# DDR3_Memory_SO-DIMM.net
KiCad netlist of a schematic drawn in Altium Designer
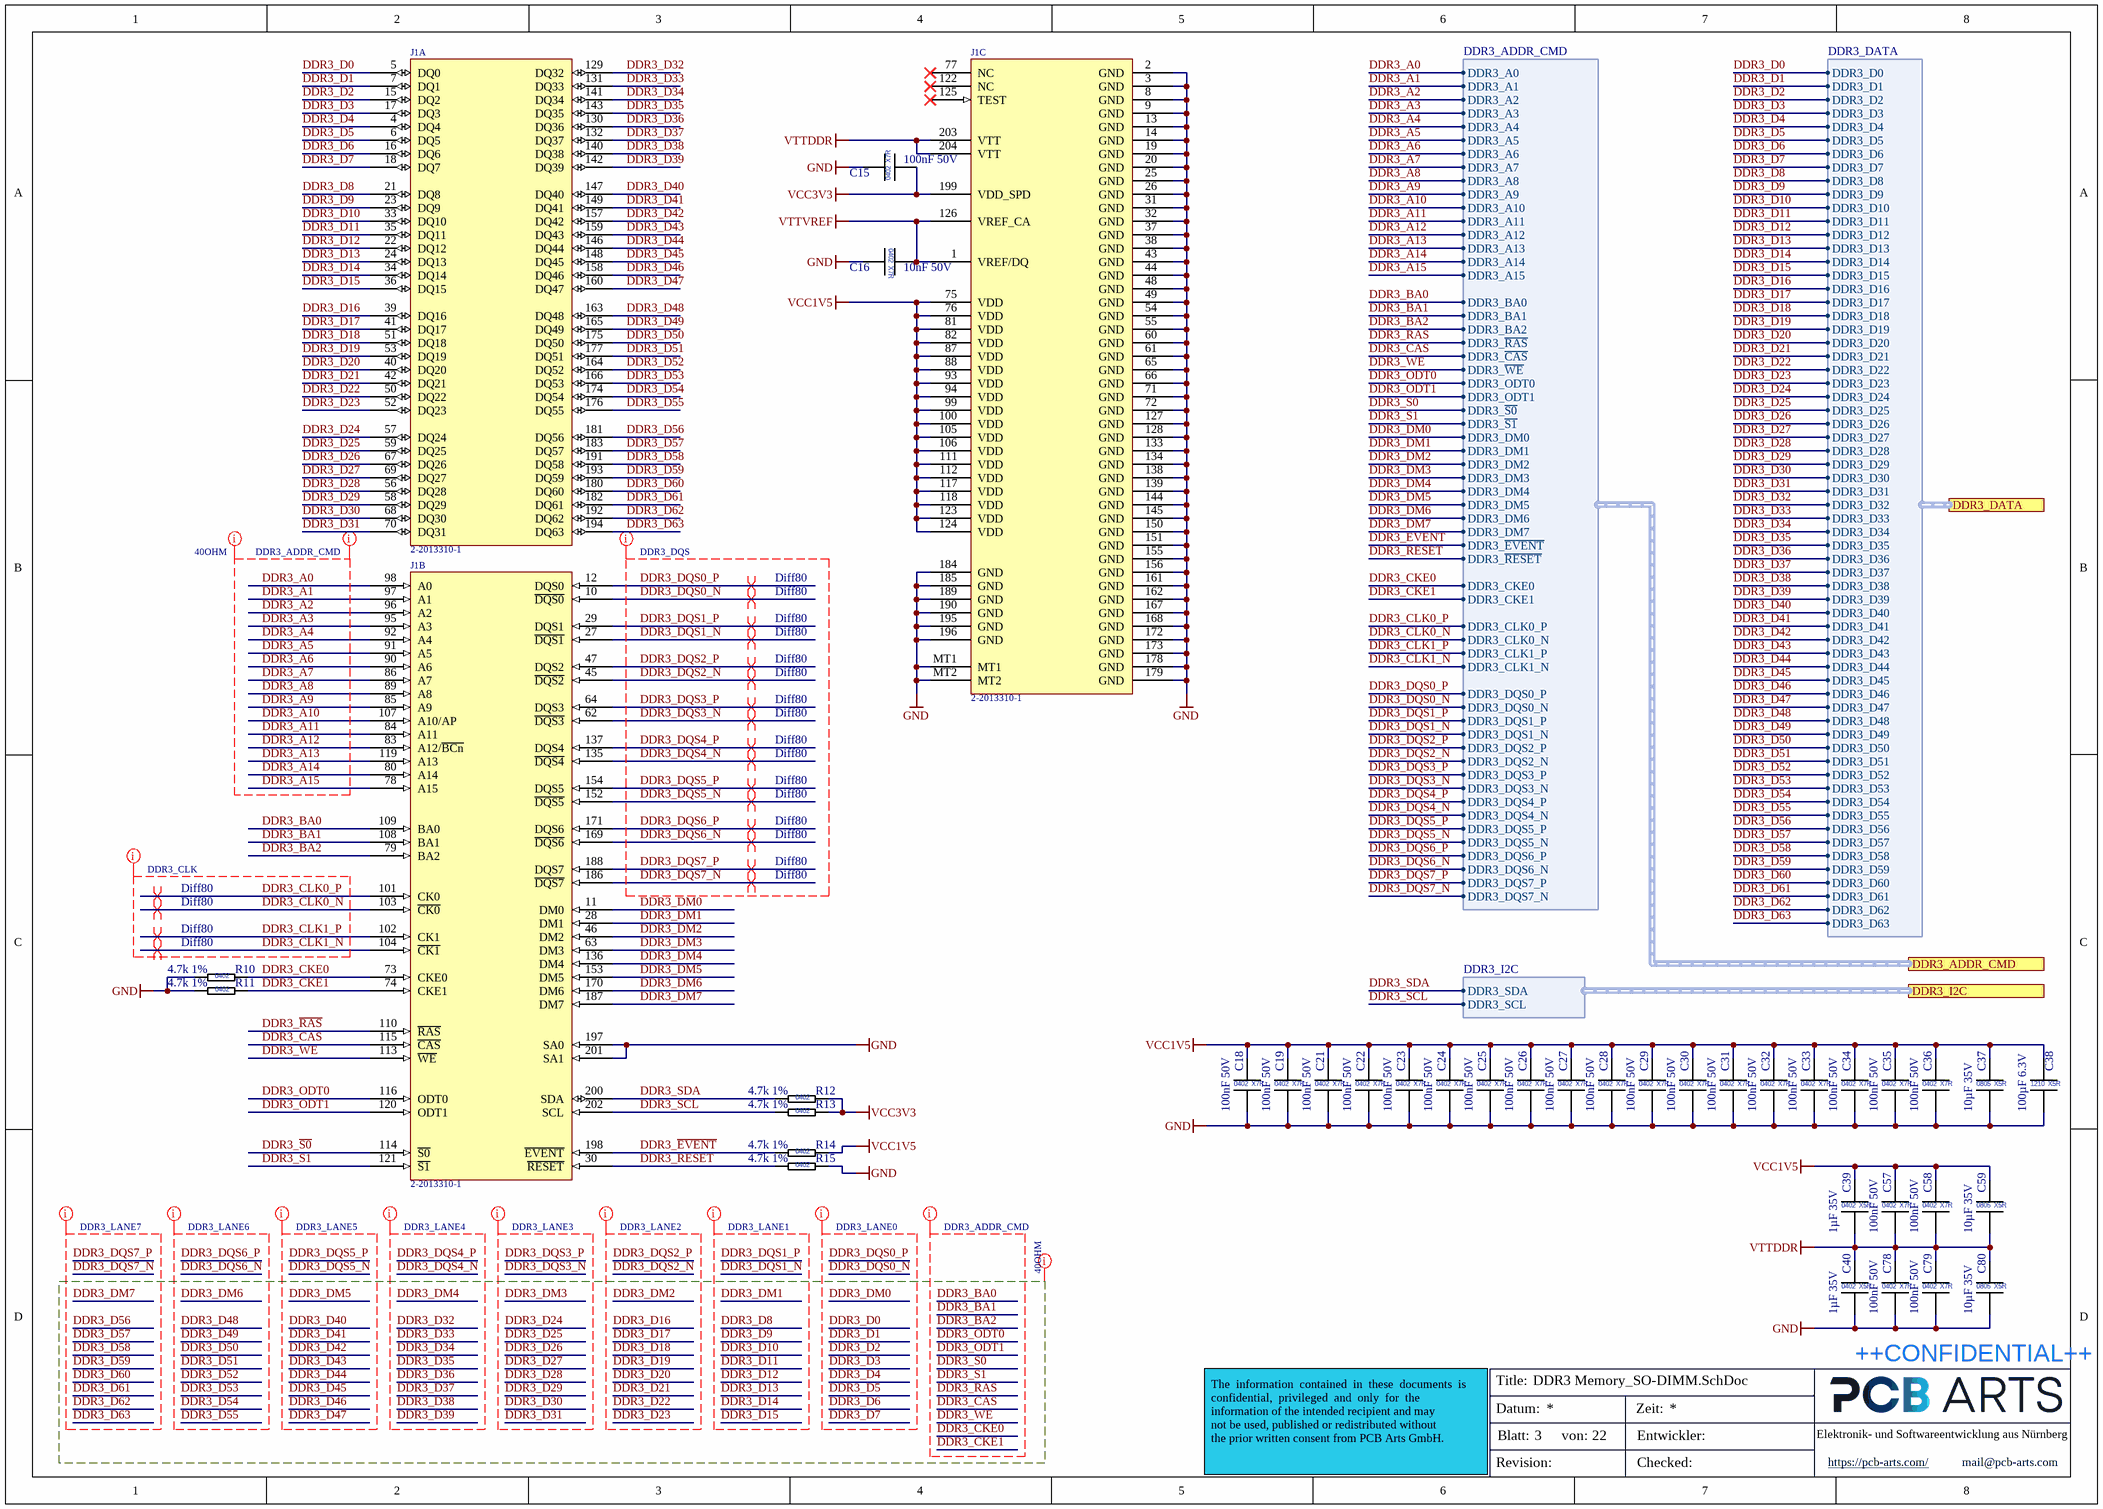
[diagram p0: DDR3 Memory_SO-DIMM.SchDoc]

(export (version "E")
  (design (tool "Eeschema 10.0.6"))
  (components
    (comp (ref "C15")
      (value "100nF 50V")
      (footprint "Cap:CAP_0402_L")
      (description "Multilayer Ceramic Capacitors MLCC - SMD/SMT 0402 50VDC")
      (libsource (lib "") (part "CAP_0402_100nF_50V_1"))
    )
    (comp (ref "C16")
      (value "10nF 50V")
      (footprint "Cap:CAP_0402_L")
      (description "Multilayer Ceramic Capacitors MLCC - SMD/SMT 0402 50VDC")
      (libsource (lib "Cap") (part "CAP_0402_10nF_50V"))
    )
    (comp (ref "C18")
      (value "100nF 50V")
      (footprint "Cap:CAP_0402_L")
      (description "Multilayer Ceramic Capacitors MLCC - SMD/SMT 0402 50VDC")
      (libsource (lib "Cap") (part "CAP_0402_100nF_50V"))
    )
    (comp (ref "C19")
      (value "100nF 50V")
      (footprint "Cap:CAP_0402_L")
      (description "Multilayer Ceramic Capacitors MLCC - SMD/SMT 0402 50VDC")
      (libsource (lib "Cap") (part "CAP_0402_100nF_50V"))
    )
    (comp (ref "C21")
      (value "100nF 50V")
      (footprint "Cap:CAP_0402_L")
      (description "Multilayer Ceramic Capacitors MLCC - SMD/SMT 0402 50VDC")
      (libsource (lib "Cap") (part "CAP_0402_100nF_50V"))
    )
    (comp (ref "C22")
      (value "100nF 50V")
      (footprint "Cap:CAP_0402_L")
      (description "Multilayer Ceramic Capacitors MLCC - SMD/SMT 0402 50VDC")
      (libsource (lib "Cap") (part "CAP_0402_100nF_50V"))
    )
    (comp (ref "C23")
      (value "100nF 50V")
      (footprint "Cap:CAP_0402_L")
      (description "Multilayer Ceramic Capacitors MLCC - SMD/SMT 0402 50VDC")
      (libsource (lib "Cap") (part "CAP_0402_100nF_50V"))
    )
    (comp (ref "C24")
      (value "100nF 50V")
      (footprint "Cap:CAP_0402_L")
      (description "Multilayer Ceramic Capacitors MLCC - SMD/SMT 0402 50VDC")
      (libsource (lib "Cap") (part "CAP_0402_100nF_50V"))
    )
    (comp (ref "C25")
      (value "100nF 50V")
      (footprint "Cap:CAP_0402_L")
      (description "Multilayer Ceramic Capacitors MLCC - SMD/SMT 0402 50VDC")
      (libsource (lib "Cap") (part "CAP_0402_100nF_50V"))
    )
    (comp (ref "C26")
      (value "100nF 50V")
      (footprint "Cap:CAP_0402_L")
      (description "Multilayer Ceramic Capacitors MLCC - SMD/SMT 0402 50VDC")
      (libsource (lib "Cap") (part "CAP_0402_100nF_50V"))
    )
    (comp (ref "C27")
      (value "100nF 50V")
      (footprint "Cap:CAP_0402_L")
      (description "Multilayer Ceramic Capacitors MLCC - SMD/SMT 0402 50VDC")
      (libsource (lib "Cap") (part "CAP_0402_100nF_50V"))
    )
    (comp (ref "C28")
      (value "100nF 50V")
      (footprint "Cap:CAP_0402_L")
      (description "Multilayer Ceramic Capacitors MLCC - SMD/SMT 0402 50VDC")
      (libsource (lib "Cap") (part "CAP_0402_100nF_50V"))
    )
    (comp (ref "C29")
      (value "100nF 50V")
      (footprint "Cap:CAP_0402_L")
      (description "Multilayer Ceramic Capacitors MLCC - SMD/SMT 0402 50VDC")
      (libsource (lib "Cap") (part "CAP_0402_100nF_50V"))
    )
    (comp (ref "C30")
      (value "100nF 50V")
      (footprint "Cap:CAP_0402_L")
      (description "Multilayer Ceramic Capacitors MLCC - SMD/SMT 0402 50VDC")
      (libsource (lib "Cap") (part "CAP_0402_100nF_50V"))
    )
    (comp (ref "C31")
      (value "100nF 50V")
      (footprint "Cap:CAP_0402_L")
      (description "Multilayer Ceramic Capacitors MLCC - SMD/SMT 0402 50VDC")
      (libsource (lib "Cap") (part "CAP_0402_100nF_50V"))
    )
    (comp (ref "C32")
      (value "100nF 50V")
      (footprint "Cap:CAP_0402_L")
      (description "Multilayer Ceramic Capacitors MLCC - SMD/SMT 0402 50VDC")
      (libsource (lib "Cap") (part "CAP_0402_100nF_50V"))
    )
    (comp (ref "C33")
      (value "100nF 50V")
      (footprint "Cap:CAP_0402_L")
      (description "Multilayer Ceramic Capacitors MLCC - SMD/SMT 0402 50VDC")
      (libsource (lib "Cap") (part "CAP_0402_100nF_50V"))
    )
    (comp (ref "C34")
      (value "100nF 50V")
      (footprint "Cap:CAP_0402_L")
      (description "Multilayer Ceramic Capacitors MLCC - SMD/SMT 0402 50VDC")
      (libsource (lib "Cap") (part "CAP_0402_100nF_50V"))
    )
    (comp (ref "C35")
      (value "100nF 50V")
      (footprint "Cap:CAP_0402_L")
      (description "Multilayer Ceramic Capacitors MLCC - SMD/SMT 0402 50VDC")
      (libsource (lib "Cap") (part "CAP_0402_100nF_50V"))
    )
    (comp (ref "C36")
      (value "100nF 50V")
      (footprint "Cap:CAP_0402_L")
      (description "Multilayer Ceramic Capacitors MLCC - SMD/SMT 0402 50VDC")
      (libsource (lib "Cap") (part "CAP_0402_100nF_50V"))
    )
    (comp (ref "C37")
      (value "10µF 35V")
      (footprint "Cap:CAP_0805")
      (description "Multilayer Ceramic Capacitors MLCC - SMD/SMT 0805 35VDC")
      (libsource (lib "Cap") (part "CAP_0805_10µF_35V"))
    )
    (comp (ref "C38")
      (value "100µF 6.3V")
      (footprint "Cap:CAP_1210")
      (description "Multilayer Ceramic Capacitors MLCC - SMD/SMT 1210 6.3VDC")
      (libsource (lib "Cap") (part "CAP_1210_100µF_6.3V"))
    )
    (comp (ref "C39")
      (value "1µF 35V")
      (footprint "Cap:CAP_0402_L")
      (description "Multilayer Ceramic Capacitors MLCC - SMD/SMT 0402 35VDC")
      (libsource (lib "Cap") (part "CAP_0402_1µF_35V"))
    )
    (comp (ref "C40")
      (value "1µF 35V")
      (footprint "Cap:CAP_0402_L")
      (description "Multilayer Ceramic Capacitors MLCC - SMD/SMT 0402 35VDC")
      (libsource (lib "Cap") (part "CAP_0402_1µF_35V"))
    )
    (comp (ref "C57")
      (value "100nF 50V")
      (footprint "Cap:CAP_0402_L")
      (description "Multilayer Ceramic Capacitors MLCC - SMD/SMT 0402 50VDC")
      (libsource (lib "Cap") (part "CAP_0402_100nF_50V"))
    )
    (comp (ref "C58")
      (value "100nF 50V")
      (footprint "Cap:CAP_0402_L")
      (description "Multilayer Ceramic Capacitors MLCC - SMD/SMT 0402 50VDC")
      (libsource (lib "Cap") (part "CAP_0402_100nF_50V"))
    )
    (comp (ref "C59")
      (value "10µF 35V")
      (footprint "Cap:CAP_0805")
      (description "Multilayer Ceramic Capacitors MLCC - SMD/SMT 0805 35VDC")
      (libsource (lib "Cap") (part "CAP_0805_10µF_35V"))
    )
    (comp (ref "C78")
      (value "100nF 50V")
      (footprint "Cap:CAP_0402_L")
      (description "Multilayer Ceramic Capacitors MLCC - SMD/SMT 0402 50VDC")
      (libsource (lib "Cap") (part "CAP_0402_100nF_50V"))
    )
    (comp (ref "C79")
      (value "100nF 50V")
      (footprint "Cap:CAP_0402_L")
      (description "Multilayer Ceramic Capacitors MLCC - SMD/SMT 0402 50VDC")
      (libsource (lib "Cap") (part "CAP_0402_100nF_50V"))
    )
    (comp (ref "C80")
      (value "10µF 35V")
      (footprint "Cap:CAP_0805")
      (description "Multilayer Ceramic Capacitors MLCC - SMD/SMT 0805 35VDC")
      (libsource (lib "Cap") (part "CAP_0805_10µF_35V"))
    )
    (comp (ref "J1")
      (value "2-2013310-1")
      (footprint "Conn:2-2013310-1")
      (description "SO-DIMM DDR3 204P 9.2H STD Connector")
      (libsource (lib "Conn") (part "2-2013310-1_SO-DIMM DDR3 204P 9.2H STD Connector"))
    )
    (comp (ref "R10")
      (value "4.7k 1%")
      (footprint "Res:RES_0402_L")
      (description "Thick Film Resistors - SMD 4.7kOhm 1%")
      (libsource (lib "Res") (part "RES_0402_4.7k_1%"))
    )
    (comp (ref "R11")
      (value "4.7k 1%")
      (footprint "Res:RES_0402_L")
      (description "Thick Film Resistors - SMD 4.7kOhm 1%")
      (libsource (lib "Res") (part "RES_0402_4.7k_1%"))
    )
    (comp (ref "R12")
      (value "4.7k 1%")
      (footprint "Res:RES_0402_L")
      (description "Thick Film Resistors - SMD 4.7kOhm 1%")
      (libsource (lib "Res") (part "RES_0402_4.7k_1%"))
    )
    (comp (ref "R13")
      (value "4.7k 1%")
      (footprint "Res:RES_0402_L")
      (description "Thick Film Resistors - SMD 4.7kOhm 1%")
      (libsource (lib "Res") (part "RES_0402_4.7k_1%"))
    )
    (comp (ref "R14")
      (value "4.7k 1%")
      (footprint "Res:RES_0402_L")
      (description "Thick Film Resistors - SMD 4.7kOhm 1%")
      (libsource (lib "Res") (part "RES_0402_4.7k_1%"))
    )
    (comp (ref "R15")
      (value "4.7k 1%")
      (footprint "Res:RES_0402_L")
      (description "Thick Film Resistors - SMD 4.7kOhm 1%")
      (libsource (lib "Res") (part "RES_0402_4.7k_1%"))
    )
  )
  (nets
    (net (code "4") (name "/DDR3_A0") (class "Default")
      (node (ref "J1") (pin "98") (pinfunction "A0_98") (pintype "input"))
    )
    (net (code "5") (name "/DDR3_A1") (class "Default")
      (node (ref "J1") (pin "97") (pinfunction "A1_97") (pintype "input"))
    )
    (net (code "6") (name "/DDR3_A2") (class "Default")
      (node (ref "J1") (pin "96") (pinfunction "A2_96") (pintype "input"))
    )
    (net (code "7") (name "/DDR3_A3") (class "Default")
      (node (ref "J1") (pin "95") (pinfunction "A3_95") (pintype "input"))
    )
    (net (code "8") (name "/DDR3_A4") (class "Default")
      (node (ref "J1") (pin "92") (pinfunction "A4_92") (pintype "input"))
    )
    (net (code "9") (name "/DDR3_A5") (class "Default")
      (node (ref "J1") (pin "91") (pinfunction "A5_91") (pintype "input"))
    )
    (net (code "10") (name "/DDR3_A6") (class "Default")
      (node (ref "J1") (pin "90") (pinfunction "A6_90") (pintype "input"))
    )
    (net (code "11") (name "/DDR3_A7") (class "Default")
      (node (ref "J1") (pin "86") (pinfunction "A7_86") (pintype "input"))
    )
    (net (code "12") (name "/DDR3_A8") (class "Default")
      (node (ref "J1") (pin "89") (pinfunction "A8_89") (pintype "input"))
    )
    (net (code "13") (name "/DDR3_A9") (class "Default")
      (node (ref "J1") (pin "85") (pinfunction "A9_85") (pintype "input"))
    )
    (net (code "14") (name "/DDR3_A10") (class "Default")
      (node (ref "J1") (pin "107") (pinfunction "A10/AP_107") (pintype "input"))
    )
    (net (code "15") (name "/DDR3_A11") (class "Default")
      (node (ref "J1") (pin "84") (pinfunction "A11_84") (pintype "input"))
    )
    (net (code "16") (name "/DDR3_A12") (class "Default")
      (node (ref "J1") (pin "83") (pinfunction "A12/~{BCn}_83") (pintype "input"))
    )
    (net (code "17") (name "/DDR3_A13") (class "Default")
      (node (ref "J1") (pin "119") (pinfunction "A13_119") (pintype "input"))
    )
    (net (code "18") (name "/DDR3_A14") (class "Default")
      (node (ref "J1") (pin "80") (pinfunction "A14_80") (pintype "input"))
    )
    (net (code "19") (name "/DDR3_A15") (class "Default")
      (node (ref "J1") (pin "78") (pinfunction "A15_78") (pintype "input"))
    )
    (net (code "20") (name "/DDR3_BA0") (class "Default")
      (node (ref "J1") (pin "109") (pinfunction "BA0_109") (pintype "input"))
    )
    (net (code "21") (name "/DDR3_BA1") (class "Default")
      (node (ref "J1") (pin "108") (pinfunction "BA1_108") (pintype "input"))
    )
    (net (code "22") (name "/DDR3_BA2") (class "Default")
      (node (ref "J1") (pin "79") (pinfunction "BA2_79") (pintype "input"))
    )
    (net (code "23") (name "/DDR3_CKE0") (class "Default")
      (node (ref "J1") (pin "73") (pinfunction "CKE0_73") (pintype "input"))
      (node (ref "R10") (pin "2") (pinfunction "2_2") (pintype "passive"))
    )
    (net (code "24") (name "/DDR3_CKE1") (class "Default")
      (node (ref "J1") (pin "74") (pinfunction "CKE1_74") (pintype "input"))
      (node (ref "R11") (pin "2") (pinfunction "2_2") (pintype "passive"))
    )
    (net (code "25") (name "/DDR3_CLK0_N") (class "Default")
      (node (ref "J1") (pin "103") (pinfunction "~{CK0}_103") (pintype "input"))
    )
    (net (code "26") (name "/DDR3_CLK0_P") (class "Default")
      (node (ref "J1") (pin "101") (pinfunction "CK0_101") (pintype "input"))
    )
    (net (code "27") (name "/DDR3_CLK1_N") (class "Default")
      (node (ref "J1") (pin "104") (pinfunction "~{CK1}_104") (pintype "input"))
    )
    (net (code "28") (name "/DDR3_CLK1_P") (class "Default")
      (node (ref "J1") (pin "102") (pinfunction "CK1_102") (pintype "input"))
    )
    (net (code "29") (name "/DDR3_D0") (class "Default")
      (node (ref "J1") (pin "5") (pinfunction "DQ0_5") (pintype "bidirectional"))
    )
    (net (code "30") (name "/DDR3_D1") (class "Default")
      (node (ref "J1") (pin "7") (pinfunction "DQ1_7") (pintype "bidirectional"))
    )
    (net (code "31") (name "/DDR3_D2") (class "Default")
      (node (ref "J1") (pin "15") (pinfunction "DQ2_15") (pintype "bidirectional"))
    )
    (net (code "32") (name "/DDR3_D3") (class "Default")
      (node (ref "J1") (pin "17") (pinfunction "DQ3_17") (pintype "bidirectional"))
    )
    (net (code "33") (name "/DDR3_D4") (class "Default")
      (node (ref "J1") (pin "4") (pinfunction "DQ4_4") (pintype "bidirectional"))
    )
    (net (code "34") (name "/DDR3_D5") (class "Default")
      (node (ref "J1") (pin "6") (pinfunction "DQ5_6") (pintype "bidirectional"))
    )
    (net (code "35") (name "/DDR3_D6") (class "Default")
      (node (ref "J1") (pin "16") (pinfunction "DQ6_16") (pintype "bidirectional"))
    )
    (net (code "36") (name "/DDR3_D7") (class "Default")
      (node (ref "J1") (pin "18") (pinfunction "DQ7_18") (pintype "bidirectional"))
    )
    (net (code "37") (name "/DDR3_D8") (class "Default")
      (node (ref "J1") (pin "21") (pinfunction "DQ8_21") (pintype "bidirectional"))
    )
    (net (code "38") (name "/DDR3_D9") (class "Default")
      (node (ref "J1") (pin "23") (pinfunction "DQ9_23") (pintype "bidirectional"))
    )
    (net (code "39") (name "/DDR3_D10") (class "Default")
      (node (ref "J1") (pin "33") (pinfunction "DQ10_33") (pintype "bidirectional"))
    )
    (net (code "40") (name "/DDR3_D11") (class "Default")
      (node (ref "J1") (pin "35") (pinfunction "DQ11_35") (pintype "bidirectional"))
    )
    (net (code "41") (name "/DDR3_D12") (class "Default")
      (node (ref "J1") (pin "22") (pinfunction "DQ12_22") (pintype "bidirectional"))
    )
    (net (code "42") (name "/DDR3_D13") (class "Default")
      (node (ref "J1") (pin "24") (pinfunction "DQ13_24") (pintype "bidirectional"))
    )
    (net (code "43") (name "/DDR3_D14") (class "Default")
      (node (ref "J1") (pin "34") (pinfunction "DQ14_34") (pintype "bidirectional"))
    )
    (net (code "44") (name "/DDR3_D15") (class "Default")
      (node (ref "J1") (pin "36") (pinfunction "DQ15_36") (pintype "bidirectional"))
    )
    (net (code "45") (name "/DDR3_D16") (class "Default")
      (node (ref "J1") (pin "39") (pinfunction "DQ16_39") (pintype "bidirectional"))
    )
    (net (code "46") (name "/DDR3_D17") (class "Default")
      (node (ref "J1") (pin "41") (pinfunction "DQ17_41") (pintype "bidirectional"))
    )
    (net (code "47") (name "/DDR3_D18") (class "Default")
      (node (ref "J1") (pin "51") (pinfunction "DQ18_51") (pintype "bidirectional"))
    )
    (net (code "48") (name "/DDR3_D19") (class "Default")
      (node (ref "J1") (pin "53") (pinfunction "DQ19_53") (pintype "bidirectional"))
    )
    (net (code "49") (name "/DDR3_D20") (class "Default")
      (node (ref "J1") (pin "40") (pinfunction "DQ20_40") (pintype "bidirectional"))
    )
    (net (code "50") (name "/DDR3_D21") (class "Default")
      (node (ref "J1") (pin "42") (pinfunction "DQ21_42") (pintype "bidirectional"))
    )
    (net (code "51") (name "/DDR3_D22") (class "Default")
      (node (ref "J1") (pin "50") (pinfunction "DQ22_50") (pintype "bidirectional"))
    )
    (net (code "52") (name "/DDR3_D23") (class "Default")
      (node (ref "J1") (pin "52") (pinfunction "DQ23_52") (pintype "bidirectional"))
    )
    (net (code "53") (name "/DDR3_D24") (class "Default")
      (node (ref "J1") (pin "57") (pinfunction "DQ24_57") (pintype "bidirectional"))
    )
    (net (code "54") (name "/DDR3_D25") (class "Default")
      (node (ref "J1") (pin "59") (pinfunction "DQ25_59") (pintype "bidirectional"))
    )
    (net (code "55") (name "/DDR3_D26") (class "Default")
      (node (ref "J1") (pin "67") (pinfunction "DQ26_67") (pintype "bidirectional"))
    )
    (net (code "56") (name "/DDR3_D27") (class "Default")
      (node (ref "J1") (pin "69") (pinfunction "DQ27_69") (pintype "bidirectional"))
    )
    (net (code "57") (name "/DDR3_D28") (class "Default")
      (node (ref "J1") (pin "56") (pinfunction "DQ28_56") (pintype "bidirectional"))
    )
    (net (code "58") (name "/DDR3_D29") (class "Default")
      (node (ref "J1") (pin "58") (pinfunction "DQ29_58") (pintype "bidirectional"))
    )
    (net (code "59") (name "/DDR3_D30") (class "Default")
      (node (ref "J1") (pin "68") (pinfunction "DQ30_68") (pintype "bidirectional"))
    )
    (net (code "60") (name "/DDR3_D31") (class "Default")
      (node (ref "J1") (pin "70") (pinfunction "DQ31_70") (pintype "bidirectional"))
    )
    (net (code "61") (name "/DDR3_D32") (class "Default")
      (node (ref "J1") (pin "129") (pinfunction "DQ32_129") (pintype "bidirectional"))
    )
    (net (code "62") (name "/DDR3_D33") (class "Default")
      (node (ref "J1") (pin "131") (pinfunction "DQ33_131") (pintype "bidirectional"))
    )
    (net (code "63") (name "/DDR3_D34") (class "Default")
      (node (ref "J1") (pin "141") (pinfunction "DQ34_141") (pintype "bidirectional"))
    )
    (net (code "64") (name "/DDR3_D35") (class "Default")
      (node (ref "J1") (pin "143") (pinfunction "DQ35_143") (pintype "bidirectional"))
    )
    (net (code "65") (name "/DDR3_D36") (class "Default")
      (node (ref "J1") (pin "130") (pinfunction "DQ36_130") (pintype "bidirectional"))
    )
    (net (code "66") (name "/DDR3_D37") (class "Default")
      (node (ref "J1") (pin "132") (pinfunction "DQ37_132") (pintype "bidirectional"))
    )
    (net (code "67") (name "/DDR3_D38") (class "Default")
      (node (ref "J1") (pin "140") (pinfunction "DQ38_140") (pintype "bidirectional"))
    )
    (net (code "68") (name "/DDR3_D39") (class "Default")
      (node (ref "J1") (pin "142") (pinfunction "DQ39_142") (pintype "bidirectional"))
    )
    (net (code "69") (name "/DDR3_D40") (class "Default")
      (node (ref "J1") (pin "147") (pinfunction "DQ40_147") (pintype "bidirectional"))
    )
    (net (code "70") (name "/DDR3_D41") (class "Default")
      (node (ref "J1") (pin "149") (pinfunction "DQ41_149") (pintype "bidirectional"))
    )
    (net (code "71") (name "/DDR3_D42") (class "Default")
      (node (ref "J1") (pin "157") (pinfunction "DQ42_157") (pintype "bidirectional"))
    )
    (net (code "72") (name "/DDR3_D43") (class "Default")
      (node (ref "J1") (pin "159") (pinfunction "DQ43_159") (pintype "bidirectional"))
    )
    (net (code "73") (name "/DDR3_D44") (class "Default")
      (node (ref "J1") (pin "146") (pinfunction "DQ44_146") (pintype "bidirectional"))
    )
    (net (code "74") (name "/DDR3_D45") (class "Default")
      (node (ref "J1") (pin "148") (pinfunction "DQ45_148") (pintype "bidirectional"))
    )
    (net (code "75") (name "/DDR3_D46") (class "Default")
      (node (ref "J1") (pin "158") (pinfunction "DQ46_158") (pintype "bidirectional"))
    )
    (net (code "76") (name "/DDR3_D47") (class "Default")
      (node (ref "J1") (pin "160") (pinfunction "DQ47_160") (pintype "bidirectional"))
    )
    (net (code "77") (name "/DDR3_D48") (class "Default")
      (node (ref "J1") (pin "163") (pinfunction "DQ48_163") (pintype "bidirectional"))
    )
    (net (code "78") (name "/DDR3_D49") (class "Default")
      (node (ref "J1") (pin "165") (pinfunction "DQ49_165") (pintype "bidirectional"))
    )
    (net (code "79") (name "/DDR3_D50") (class "Default")
      (node (ref "J1") (pin "175") (pinfunction "DQ50_175") (pintype "bidirectional"))
    )
    (net (code "80") (name "/DDR3_D51") (class "Default")
      (node (ref "J1") (pin "177") (pinfunction "DQ51_177") (pintype "bidirectional"))
    )
    (net (code "81") (name "/DDR3_D52") (class "Default")
      (node (ref "J1") (pin "164") (pinfunction "DQ52_164") (pintype "bidirectional"))
    )
    (net (code "82") (name "/DDR3_D53") (class "Default")
      (node (ref "J1") (pin "166") (pinfunction "DQ53_166") (pintype "bidirectional"))
    )
    (net (code "83") (name "/DDR3_D54") (class "Default")
      (node (ref "J1") (pin "174") (pinfunction "DQ54_174") (pintype "bidirectional"))
    )
    (net (code "84") (name "/DDR3_D55") (class "Default")
      (node (ref "J1") (pin "176") (pinfunction "DQ55_176") (pintype "bidirectional"))
    )
    (net (code "85") (name "/DDR3_D56") (class "Default")
      (node (ref "J1") (pin "181") (pinfunction "DQ56_181") (pintype "bidirectional"))
    )
    (net (code "86") (name "/DDR3_D57") (class "Default")
      (node (ref "J1") (pin "183") (pinfunction "DQ57_183") (pintype "bidirectional"))
    )
    (net (code "87") (name "/DDR3_D58") (class "Default")
      (node (ref "J1") (pin "191") (pinfunction "DQ58_191") (pintype "bidirectional"))
    )
    (net (code "88") (name "/DDR3_D59") (class "Default")
      (node (ref "J1") (pin "193") (pinfunction "DQ59_193") (pintype "bidirectional"))
    )
    (net (code "89") (name "/DDR3_D60") (class "Default")
      (node (ref "J1") (pin "180") (pinfunction "DQ60_180") (pintype "bidirectional"))
    )
    (net (code "90") (name "/DDR3_D61") (class "Default")
      (node (ref "J1") (pin "182") (pinfunction "DQ61_182") (pintype "bidirectional"))
    )
    (net (code "91") (name "/DDR3_D62") (class "Default")
      (node (ref "J1") (pin "192") (pinfunction "DQ62_192") (pintype "bidirectional"))
    )
    (net (code "92") (name "/DDR3_D63") (class "Default")
      (node (ref "J1") (pin "194") (pinfunction "DQ63_194") (pintype "bidirectional"))
    )
    (net (code "93") (name "/DDR3_DM0") (class "Default")
      (node (ref "J1") (pin "11") (pinfunction "DM0_11") (pintype "input"))
    )
    (net (code "94") (name "/DDR3_DM1") (class "Default")
      (node (ref "J1") (pin "28") (pinfunction "DM1_28") (pintype "input"))
    )
    (net (code "95") (name "/DDR3_DM2") (class "Default")
      (node (ref "J1") (pin "46") (pinfunction "DM2_46") (pintype "input"))
    )
    (net (code "96") (name "/DDR3_DM3") (class "Default")
      (node (ref "J1") (pin "63") (pinfunction "DM3_63") (pintype "input"))
    )
    (net (code "97") (name "/DDR3_DM4") (class "Default")
      (node (ref "J1") (pin "136") (pinfunction "DM4_136") (pintype "input"))
    )
    (net (code "98") (name "/DDR3_DM5") (class "Default")
      (node (ref "J1") (pin "153") (pinfunction "DM5_153") (pintype "input"))
    )
    (net (code "99") (name "/DDR3_DM6") (class "Default")
      (node (ref "J1") (pin "170") (pinfunction "DM6_170") (pintype "input"))
    )
    (net (code "100") (name "/DDR3_DM7") (class "Default")
      (node (ref "J1") (pin "187") (pinfunction "DM7_187") (pintype "input"))
    )
    (net (code "101") (name "/DDR3_DQS0_N") (class "Default")
      (node (ref "J1") (pin "10") (pinfunction "~{DQS0}_10") (pintype "input"))
    )
    (net (code "102") (name "/DDR3_DQS0_P") (class "Default")
      (node (ref "J1") (pin "12") (pinfunction "DQS0_12") (pintype "input"))
    )
    (net (code "103") (name "/DDR3_DQS1_N") (class "Default")
      (node (ref "J1") (pin "27") (pinfunction "~{DQS1}_27") (pintype "input"))
    )
    (net (code "104") (name "/DDR3_DQS1_P") (class "Default")
      (node (ref "J1") (pin "29") (pinfunction "DQS1_29") (pintype "input"))
    )
    (net (code "105") (name "/DDR3_DQS2_N") (class "Default")
      (node (ref "J1") (pin "45") (pinfunction "~{DQS2}_45") (pintype "input"))
    )
    (net (code "106") (name "/DDR3_DQS2_P") (class "Default")
      (node (ref "J1") (pin "47") (pinfunction "DQS2_47") (pintype "input"))
    )
    (net (code "107") (name "/DDR3_DQS3_N") (class "Default")
      (node (ref "J1") (pin "62") (pinfunction "~{DQS3}_62") (pintype "input"))
    )
    (net (code "108") (name "/DDR3_DQS3_P") (class "Default")
      (node (ref "J1") (pin "64") (pinfunction "DQS3_64") (pintype "input"))
    )
    (net (code "109") (name "/DDR3_DQS4_N") (class "Default")
      (node (ref "J1") (pin "135") (pinfunction "~{DQS4}_135") (pintype "input"))
    )
    (net (code "110") (name "/DDR3_DQS4_P") (class "Default")
      (node (ref "J1") (pin "137") (pinfunction "DQS4_137") (pintype "input"))
    )
    (net (code "111") (name "/DDR3_DQS5_N") (class "Default")
      (node (ref "J1") (pin "152") (pinfunction "~{DQS5}_152") (pintype "input"))
    )
    (net (code "112") (name "/DDR3_DQS5_P") (class "Default")
      (node (ref "J1") (pin "154") (pinfunction "DQS5_154") (pintype "input"))
    )
    (net (code "113") (name "/DDR3_DQS6_N") (class "Default")
      (node (ref "J1") (pin "169") (pinfunction "~{DQS6}_169") (pintype "input"))
    )
    (net (code "114") (name "/DDR3_DQS6_P") (class "Default")
      (node (ref "J1") (pin "171") (pinfunction "DQS6_171") (pintype "input"))
    )
    (net (code "115") (name "/DDR3_DQS7_N") (class "Default")
      (node (ref "J1") (pin "186") (pinfunction "~{DQS7}_186") (pintype "input"))
    )
    (net (code "116") (name "/DDR3_DQS7_P") (class "Default")
      (node (ref "J1") (pin "188") (pinfunction "DQS7_188") (pintype "input"))
    )
    (net (code "117") (name "/DDR3_ODT0") (class "Default")
      (node (ref "J1") (pin "116") (pinfunction "ODT0_116") (pintype "input"))
    )
    (net (code "118") (name "/DDR3_ODT1") (class "Default")
      (node (ref "J1") (pin "120") (pinfunction "ODT1_120") (pintype "input"))
    )
    (net (code "119") (name "/DDR3_SCL") (class "Default")
      (node (ref "J1") (pin "202") (pinfunction "SCL_202") (pintype "input"))
      (node (ref "R13") (pin "1") (pinfunction "1_1") (pintype "passive"))
    )
    (net (code "120") (name "/DDR3_SDA") (class "Default")
      (node (ref "J1") (pin "200") (pinfunction "SDA_200") (pintype "bidirectional"))
      (node (ref "R12") (pin "1") (pinfunction "1_1") (pintype "passive"))
    )
    (net (code "121") (name "/DDR3_~{CAS}") (class "Default")
      (node (ref "J1") (pin "115") (pinfunction "~{CAS}_115") (pintype "input"))
    )
    (net (code "122") (name "/DDR3_~{EVENT}") (class "Default")
      (node (ref "J1") (pin "198") (pinfunction "~{EVENT}_198") (pintype "input"))
      (node (ref "R14") (pin "1") (pinfunction "1_1") (pintype "passive"))
    )
    (net (code "123") (name "/DDR3_~{RAS}") (class "Default")
      (node (ref "J1") (pin "110") (pinfunction "~{RAS}_110") (pintype "input"))
    )
    (net (code "124") (name "/DDR3_~{RESET}") (class "Default")
      (node (ref "J1") (pin "30") (pinfunction "~{RESET}_30") (pintype "input"))
      (node (ref "R15") (pin "1") (pinfunction "1_1") (pintype "passive"))
    )
    (net (code "125") (name "/DDR3_~{S0}") (class "Default")
      (node (ref "J1") (pin "114") (pinfunction "~{S0}_114") (pintype "input"))
    )
    (net (code "126") (name "/DDR3_~{S1}") (class "Default")
      (node (ref "J1") (pin "121") (pinfunction "~{S1}_121") (pintype "input"))
    )
    (net (code "127") (name "/DDR3_~{WE}") (class "Default")
      (node (ref "J1") (pin "113") (pinfunction "~{WE}_113") (pintype "input"))
    )
    (net (code "131") (name "GND") (class "Default")
      (node (ref "C15") (pin "1") (pinfunction "1_1") (pintype "passive"))
      (node (ref "C16") (pin "2") (pinfunction "2_2") (pintype "passive"))
      (node (ref "C18") (pin "2") (pinfunction "2_2") (pintype "passive"))
      (node (ref "C19") (pin "2") (pinfunction "2_2") (pintype "passive"))
      (node (ref "C21") (pin "2") (pinfunction "2_2") (pintype "passive"))
      (node (ref "C22") (pin "2") (pinfunction "2_2") (pintype "passive"))
      (node (ref "C23") (pin "2") (pinfunction "2_2") (pintype "passive"))
      (node (ref "C24") (pin "2") (pinfunction "2_2") (pintype "passive"))
      (node (ref "C25") (pin "2") (pinfunction "2_2") (pintype "passive"))
      (node (ref "C26") (pin "2") (pinfunction "2_2") (pintype "passive"))
      (node (ref "C27") (pin "2") (pinfunction "2_2") (pintype "passive"))
      (node (ref "C28") (pin "2") (pinfunction "2_2") (pintype "passive"))
      (node (ref "C29") (pin "2") (pinfunction "2_2") (pintype "passive"))
      (node (ref "C30") (pin "2") (pinfunction "2_2") (pintype "passive"))
      (node (ref "C31") (pin "2") (pinfunction "2_2") (pintype "passive"))
      (node (ref "C32") (pin "2") (pinfunction "2_2") (pintype "passive"))
      (node (ref "C33") (pin "2") (pinfunction "2_2") (pintype "passive"))
      (node (ref "C34") (pin "2") (pinfunction "2_2") (pintype "passive"))
      (node (ref "C35") (pin "2") (pinfunction "2_2") (pintype "passive"))
      (node (ref "C36") (pin "2") (pinfunction "2_2") (pintype "passive"))
      (node (ref "C37") (pin "2") (pinfunction "2_2") (pintype "passive"))
      (node (ref "C38") (pin "2") (pinfunction "2_2") (pintype "passive"))
      (node (ref "C40") (pin "2") (pinfunction "2_2") (pintype "passive"))
      (node (ref "C78") (pin "2") (pinfunction "2_2") (pintype "passive"))
      (node (ref "C79") (pin "2") (pinfunction "2_2") (pintype "passive"))
      (node (ref "C80") (pin "2") (pinfunction "2_2") (pintype "passive"))
      (node (ref "J1") (pin "127") (pinfunction "GND_127") (pintype "power_in"))
      (node (ref "J1") (pin "128") (pinfunction "GND_128") (pintype "power_in"))
      (node (ref "J1") (pin "13") (pinfunction "GND_13") (pintype "power_in"))
      (node (ref "J1") (pin "133") (pinfunction "GND_133") (pintype "power_in"))
      (node (ref "J1") (pin "134") (pinfunction "GND_134") (pintype "power_in"))
      (node (ref "J1") (pin "138") (pinfunction "GND_138") (pintype "power_in"))
      (node (ref "J1") (pin "139") (pinfunction "GND_139") (pintype "power_in"))
      (node (ref "J1") (pin "14") (pinfunction "GND_14") (pintype "power_in"))
      (node (ref "J1") (pin "144") (pinfunction "GND_144") (pintype "power_in"))
      (node (ref "J1") (pin "145") (pinfunction "GND_145") (pintype "power_in"))
      (node (ref "J1") (pin "150") (pinfunction "GND_150") (pintype "power_in"))
      (node (ref "J1") (pin "151") (pinfunction "GND_151") (pintype "power_in"))
      (node (ref "J1") (pin "155") (pinfunction "GND_155") (pintype "power_in"))
      (node (ref "J1") (pin "156") (pinfunction "GND_156") (pintype "power_in"))
      (node (ref "J1") (pin "161") (pinfunction "GND_161") (pintype "power_in"))
      (node (ref "J1") (pin "162") (pinfunction "GND_162") (pintype "power_in"))
      (node (ref "J1") (pin "167") (pinfunction "GND_167") (pintype "power_in"))
      (node (ref "J1") (pin "168") (pinfunction "GND_168") (pintype "power_in"))
      (node (ref "J1") (pin "172") (pinfunction "GND_172") (pintype "power_in"))
      (node (ref "J1") (pin "173") (pinfunction "GND_173") (pintype "power_in"))
      (node (ref "J1") (pin "178") (pinfunction "GND_178") (pintype "power_in"))
      (node (ref "J1") (pin "179") (pinfunction "GND_179") (pintype "power_in"))
      (node (ref "J1") (pin "184") (pinfunction "GND_184") (pintype "power_in"))
      (node (ref "J1") (pin "185") (pinfunction "GND_185") (pintype "power_in"))
      (node (ref "J1") (pin "189") (pinfunction "GND_189") (pintype "power_in"))
      (node (ref "J1") (pin "19") (pinfunction "GND_19") (pintype "power_in"))
      (node (ref "J1") (pin "190") (pinfunction "GND_190") (pintype "power_in"))
      (node (ref "J1") (pin "195") (pinfunction "GND_195") (pintype "power_in"))
      (node (ref "J1") (pin "196") (pinfunction "GND_196") (pintype "power_in"))
      (node (ref "J1") (pin "197") (pinfunction "SA0_197") (pintype "input"))
      (node (ref "J1") (pin "2") (pinfunction "GND_2") (pintype "power_in"))
      (node (ref "J1") (pin "20") (pinfunction "GND_20") (pintype "power_in"))
      (node (ref "J1") (pin "201") (pinfunction "SA1_201") (pintype "input"))
      (node (ref "J1") (pin "25") (pinfunction "GND_25") (pintype "power_in"))
      (node (ref "J1") (pin "26") (pinfunction "GND_26") (pintype "power_in"))
      (node (ref "J1") (pin "3") (pinfunction "GND_3") (pintype "power_in"))
      (node (ref "J1") (pin "31") (pinfunction "GND_31") (pintype "power_in"))
      (node (ref "J1") (pin "32") (pinfunction "GND_32") (pintype "power_in"))
      (node (ref "J1") (pin "37") (pinfunction "GND_37") (pintype "power_in"))
      (node (ref "J1") (pin "38") (pinfunction "GND_38") (pintype "power_in"))
      (node (ref "J1") (pin "43") (pinfunction "GND_43") (pintype "power_in"))
      (node (ref "J1") (pin "44") (pinfunction "GND_44") (pintype "power_in"))
      (node (ref "J1") (pin "48") (pinfunction "GND_48") (pintype "power_in"))
      (node (ref "J1") (pin "49") (pinfunction "GND_49") (pintype "power_in"))
      (node (ref "J1") (pin "54") (pinfunction "GND_54") (pintype "power_in"))
      (node (ref "J1") (pin "55") (pinfunction "GND_55") (pintype "power_in"))
      (node (ref "J1") (pin "60") (pinfunction "GND_60") (pintype "power_in"))
      (node (ref "J1") (pin "61") (pinfunction "GND_61") (pintype "power_in"))
      (node (ref "J1") (pin "65") (pinfunction "GND_65") (pintype "power_in"))
      (node (ref "J1") (pin "66") (pinfunction "GND_66") (pintype "power_in"))
      (node (ref "J1") (pin "71") (pinfunction "GND_71") (pintype "power_in"))
      (node (ref "J1") (pin "72") (pinfunction "GND_72") (pintype "power_in"))
      (node (ref "J1") (pin "8") (pinfunction "GND_8") (pintype "power_in"))
      (node (ref "J1") (pin "9") (pinfunction "GND_9") (pintype "power_in"))
      (node (ref "J1") (pin "MT1") (pinfunction "MT1_MT1") (pintype "power_in"))
      (node (ref "J1") (pin "MT2") (pinfunction "MT2_MT2") (pintype "power_in"))
      (node (ref "R10") (pin "1") (pinfunction "1_1") (pintype "passive"))
      (node (ref "R11") (pin "1") (pinfunction "1_1") (pintype "passive"))
      (node (ref "R15") (pin "2") (pinfunction "2_2") (pintype "passive"))
    )
    (net (code "132") (name "VCC1V5") (class "Default")
      (node (ref "C18") (pin "1") (pinfunction "1_1") (pintype "passive"))
      (node (ref "C19") (pin "1") (pinfunction "1_1") (pintype "passive"))
      (node (ref "C21") (pin "1") (pinfunction "1_1") (pintype "passive"))
      (node (ref "C22") (pin "1") (pinfunction "1_1") (pintype "passive"))
      (node (ref "C23") (pin "1") (pinfunction "1_1") (pintype "passive"))
      (node (ref "C24") (pin "1") (pinfunction "1_1") (pintype "passive"))
      (node (ref "C25") (pin "1") (pinfunction "1_1") (pintype "passive"))
      (node (ref "C26") (pin "1") (pinfunction "1_1") (pintype "passive"))
      (node (ref "C27") (pin "1") (pinfunction "1_1") (pintype "passive"))
      (node (ref "C28") (pin "1") (pinfunction "1_1") (pintype "passive"))
      (node (ref "C29") (pin "1") (pinfunction "1_1") (pintype "passive"))
      (node (ref "C30") (pin "1") (pinfunction "1_1") (pintype "passive"))
      (node (ref "C31") (pin "1") (pinfunction "1_1") (pintype "passive"))
      (node (ref "C32") (pin "1") (pinfunction "1_1") (pintype "passive"))
      (node (ref "C33") (pin "1") (pinfunction "1_1") (pintype "passive"))
      (node (ref "C34") (pin "1") (pinfunction "1_1") (pintype "passive"))
      (node (ref "C35") (pin "1") (pinfunction "1_1") (pintype "passive"))
      (node (ref "C36") (pin "1") (pinfunction "1_1") (pintype "passive"))
      (node (ref "C37") (pin "1") (pinfunction "1_1") (pintype "passive"))
      (node (ref "C38") (pin "1") (pinfunction "1_1") (pintype "passive"))
      (node (ref "C39") (pin "1") (pinfunction "1_1") (pintype "passive"))
      (node (ref "C57") (pin "1") (pinfunction "1_1") (pintype "passive"))
      (node (ref "C58") (pin "1") (pinfunction "1_1") (pintype "passive"))
      (node (ref "C59") (pin "1") (pinfunction "1_1") (pintype "passive"))
      (node (ref "J1") (pin "100") (pinfunction "VDD_100") (pintype "power_in"))
      (node (ref "J1") (pin "105") (pinfunction "VDD_105") (pintype "power_in"))
      (node (ref "J1") (pin "106") (pinfunction "VDD_106") (pintype "power_in"))
      (node (ref "J1") (pin "111") (pinfunction "VDD_111") (pintype "power_in"))
      (node (ref "J1") (pin "112") (pinfunction "VDD_112") (pintype "power_in"))
      (node (ref "J1") (pin "117") (pinfunction "VDD_117") (pintype "power_in"))
      (node (ref "J1") (pin "118") (pinfunction "VDD_118") (pintype "power_in"))
      (node (ref "J1") (pin "123") (pinfunction "VDD_123") (pintype "power_in"))
      (node (ref "J1") (pin "124") (pinfunction "VDD_124") (pintype "power_in"))
      (node (ref "J1") (pin "75") (pinfunction "VDD_75") (pintype "power_in"))
      (node (ref "J1") (pin "76") (pinfunction "VDD_76") (pintype "power_in"))
      (node (ref "J1") (pin "81") (pinfunction "VDD_81") (pintype "power_in"))
      (node (ref "J1") (pin "82") (pinfunction "VDD_82") (pintype "power_in"))
      (node (ref "J1") (pin "87") (pinfunction "VDD_87") (pintype "power_in"))
      (node (ref "J1") (pin "88") (pinfunction "VDD_88") (pintype "power_in"))
      (node (ref "J1") (pin "93") (pinfunction "VDD_93") (pintype "power_in"))
      (node (ref "J1") (pin "94") (pinfunction "VDD_94") (pintype "power_in"))
      (node (ref "J1") (pin "99") (pinfunction "VDD_99") (pintype "power_in"))
      (node (ref "R14") (pin "2") (pinfunction "2_2") (pintype "passive"))
    )
    (net (code "133") (name "VCC3V3") (class "Default")
      (node (ref "C15") (pin "2") (pinfunction "2_2") (pintype "passive"))
      (node (ref "J1") (pin "199") (pinfunction "VDD_SPD_199") (pintype "power_in"))
      (node (ref "R12") (pin "2") (pinfunction "2_2") (pintype "passive"))
      (node (ref "R13") (pin "2") (pinfunction "2_2") (pintype "passive"))
    )
    (net (code "134") (name "VTTDDR") (class "Default")
      (node (ref "C39") (pin "2") (pinfunction "2_2") (pintype "passive"))
      (node (ref "C40") (pin "1") (pinfunction "1_1") (pintype "passive"))
      (node (ref "C57") (pin "2") (pinfunction "2_2") (pintype "passive"))
      (node (ref "C58") (pin "2") (pinfunction "2_2") (pintype "passive"))
      (node (ref "C59") (pin "2") (pinfunction "2_2") (pintype "passive"))
      (node (ref "C78") (pin "1") (pinfunction "1_1") (pintype "passive"))
      (node (ref "C79") (pin "1") (pinfunction "1_1") (pintype "passive"))
      (node (ref "C80") (pin "1") (pinfunction "1_1") (pintype "passive"))
      (node (ref "J1") (pin "203") (pinfunction "VTT_203") (pintype "power_in"))
      (node (ref "J1") (pin "204") (pinfunction "VTT_204") (pintype "power_in"))
    )
    (net (code "135") (name "VTTVREF") (class "Default")
      (node (ref "C16") (pin "1") (pinfunction "1_1") (pintype "passive"))
      (node (ref "J1") (pin "1") (pinfunction "VREF/DQ_1") (pintype "power_in"))
      (node (ref "J1") (pin "126") (pinfunction "VREF_CA_126") (pintype "power_in"))
    )
    (net (code "136") (name "unconnected-(J1C-NC-Pad77)") (class "Default")
      (node (ref "J1") (pin "77") (pinfunction "NC_77") (pintype "passive+no_connect"))
    )
    (net (code "137") (name "unconnected-(J1C-NC-Pad122)") (class "Default")
      (node (ref "J1") (pin "122") (pinfunction "NC_122") (pintype "passive+no_connect"))
    )
    (net (code "138") (name "unconnected-(J1C-TEST-Pad125)") (class "Default")
      (node (ref "J1") (pin "125") (pinfunction "TEST_125") (pintype "input+no_connect"))
    )
  )
)
